# 04_-_SERVO_DRIVER.net
KiCad netlist of a schematic drawn in Altium Designer
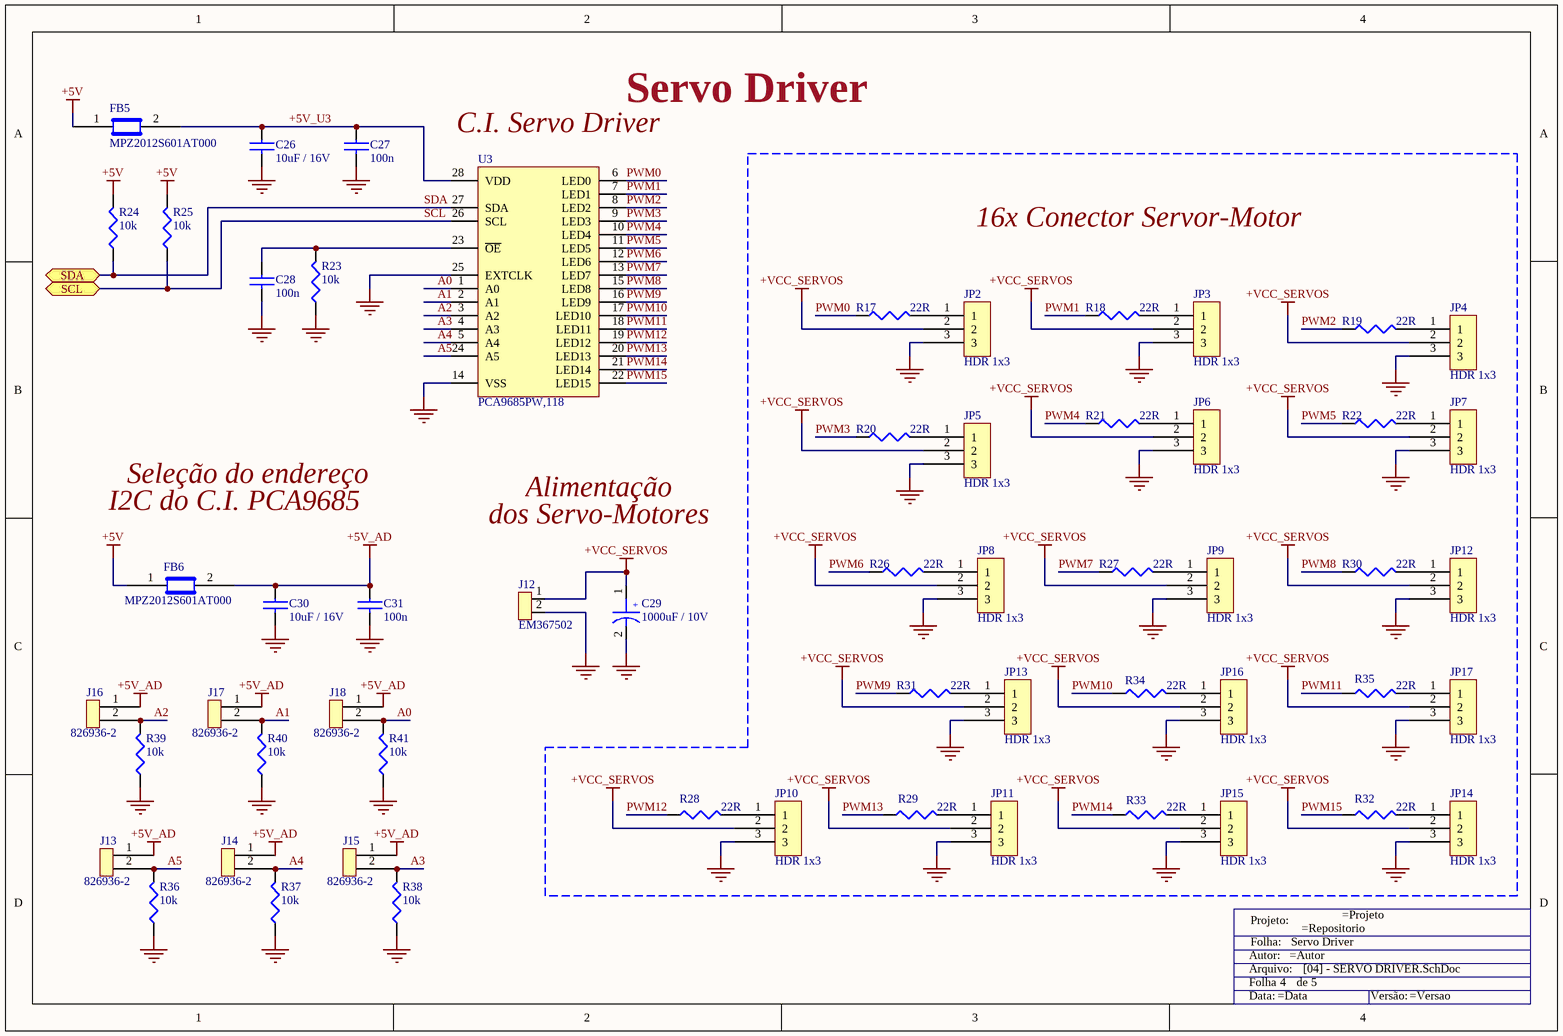
[diagram p0: [04] - SERVO DRIVER.SchDoc]

(export (version "E")
  (design (tool "Eeschema 10.0.6"))
  (components
    (comp (ref "C26")
      (value "10uF / 16V")
      (footprint "C0805")
      (description "CAP CER 10UF 16V X5R 0805")
      (fields
        (field (name "MANUFACTURER") "TDK Corporation")
        (field (name "MANUFACTURER PART NUMBER") "C2012X5R1C106M125AC")
      )
      (libsource (lib "Servo_Control_Lib") (part "C2012X5R1C106M125AC"))
    )
    (comp (ref "C27")
      (value "100n")
      (footprint "C0805")
      (description "CAP CER 0.1UF 50V X7R 0805")
      (fields
        (field (name "MANUFACTURER") "TDK Corporation")
        (field (name "MANUFACTURER PART NUMBER") "C2012X7R1H104K085AA")
      )
      (libsource (lib "Servo_Control_Lib") (part "C2012X7R1H104K085AA_1"))
    )
    (comp (ref "C28")
      (value "100n")
      (footprint "C0805")
      (description "CAP CER 0.1UF 50V X7R 0805")
      (fields
        (field (name "MANUFACTURER") "TDK Corporation")
        (field (name "MANUFACTURER PART NUMBER") "C2012X7R1H104K085AA")
      )
      (libsource (lib "Servo_Control_Lib") (part "C2012X7R1H104K085AA_1"))
    )
    (comp (ref "C29")
      (value "1000uF / 10V")
      (footprint "CAP_EL_10MMX16")
      (description "Aluminum Electrolytic Capacitors - Leaded 10volts 1000uF 10X16")
      (fields
        (field (name "MANUFACTURER") "United Chemi-Con")
        (field (name "MANUFACTURER PART NUMBER") "EKZE100ELL102MJ16S")
      )
      (libsource (lib "Servo_Control_Lib") (part "EKZE100ELL102MJ16S"))
    )
    (comp (ref "C30")
      (value "10uF / 16V")
      (footprint "C0805")
      (description "CAP CER 10UF 16V X5R 0805")
      (fields
        (field (name "MANUFACTURER") "TDK Corporation")
        (field (name "MANUFACTURER PART NUMBER") "C2012X5R1C106M125AC")
      )
      (libsource (lib "Servo_Control_Lib") (part "C2012X5R1C106M125AC"))
    )
    (comp (ref "C31")
      (value "100n")
      (footprint "C0805")
      (description "CAP CER 0.1UF 50V X7R 0805")
      (fields
        (field (name "MANUFACTURER") "TDK Corporation")
        (field (name "MANUFACTURER PART NUMBER") "C2012X7R1H104K085AA")
      )
      (libsource (lib "Servo_Control_Lib") (part "C2012X7R1H104K085AA_1"))
    )
    (comp (ref "FB5")
      (value "MPZ2012S601AT000")
      (footprint "C0805")
      (description "FERRITE CHIP BEAD 600 OHM SMD")
      (fields (field (name "MANUFACTURER") "TDK Corporation"))
      (libsource (lib "Servo_Control_Lib") (part "MPZ2012S601AT000"))
    )
    (comp (ref "FB6")
      (value "MPZ2012S601AT000")
      (footprint "C0805")
      (description "FERRITE CHIP BEAD 600 OHM SMD")
      (fields (field (name "MANUFACTURER") "TDK Corporation"))
      (libsource (lib "Servo_Control_Lib") (part "MPZ2012S601AT000"))
    )
    (comp (ref "J12")
      (value "EM367502")
      (footprint "2_Pins_Fixed_Terminal")
      (description "Fixed Terminal Blocks EURO (MA311-50002) TERM")
      (fields (field (name "MANUFACTURER") "Bussmann / Eaton"))
      (libsource (lib "Servo_Control_Lib") (part "EM367502"))
    )
    (comp (ref "J13")
      (value "826936-2")
      (footprint "HDR_1X2_2.54MM")
      (description "Headers & Wire Housings 2P SINGLE ROW")
      (fields (field (name "MANUFACTURER") "TE Connectivity"))
      (libsource (lib "Servo_Control_Lib") (part "826936-2"))
    )
    (comp (ref "J14")
      (value "826936-2")
      (footprint "HDR_1X2_2.54MM")
      (description "Headers & Wire Housings 2P SINGLE ROW")
      (fields (field (name "MANUFACTURER") "TE Connectivity"))
      (libsource (lib "Servo_Control_Lib") (part "826936-2"))
    )
    (comp (ref "J15")
      (value "826936-2")
      (footprint "HDR_1X2_2.54MM")
      (description "Headers & Wire Housings 2P SINGLE ROW")
      (fields (field (name "MANUFACTURER") "TE Connectivity"))
      (libsource (lib "Servo_Control_Lib") (part "826936-2"))
    )
    (comp (ref "J16")
      (value "826936-2")
      (footprint "HDR_1X2_2.54MM")
      (description "Headers & Wire Housings 2P SINGLE ROW")
      (fields (field (name "MANUFACTURER") "TE Connectivity"))
      (libsource (lib "Servo_Control_Lib") (part "826936-2"))
    )
    (comp (ref "J17")
      (value "826936-2")
      (footprint "HDR_1X2_2.54MM")
      (description "Headers & Wire Housings 2P SINGLE ROW")
      (fields (field (name "MANUFACTURER") "TE Connectivity"))
      (libsource (lib "Servo_Control_Lib") (part "826936-2"))
    )
    (comp (ref "J18")
      (value "826936-2")
      (footprint "HDR_1X2_2.54MM")
      (description "Headers & Wire Housings 2P SINGLE ROW")
      (fields (field (name "MANUFACTURER") "TE Connectivity"))
      (libsource (lib "Servo_Control_Lib") (part "826936-2"))
    )
    (comp (ref "JP2")
      (value "HDR 1x3")
      (footprint "Hdr_1x3_2.54mm")
      (description "BERGSTIK II .100\" SR STRAIGHT")
      (fields (field (name "MANUFACTURER") "FCI") (field (name "MANUFACTURER PART NUMBER") "68000-103HLF"))
      (libsource (lib "Servo_Control_Lib") (part "68000-103HLF"))
    )
    (comp (ref "JP3")
      (value "HDR 1x3")
      (footprint "Hdr_1x3_2.54mm")
      (description "BERGSTIK II .100\" SR STRAIGHT")
      (fields (field (name "MANUFACTURER") "FCI") (field (name "MANUFACTURER PART NUMBER") "68000-103HLF"))
      (libsource (lib "Servo_Control_Lib") (part "68000-103HLF"))
    )
    (comp (ref "JP4")
      (value "HDR 1x3")
      (footprint "Hdr_1x3_2.54mm")
      (description "BERGSTIK II .100\" SR STRAIGHT")
      (fields (field (name "MANUFACTURER") "FCI") (field (name "MANUFACTURER PART NUMBER") "68000-103HLF"))
      (libsource (lib "Servo_Control_Lib") (part "68000-103HLF"))
    )
    (comp (ref "JP5")
      (value "HDR 1x3")
      (footprint "Hdr_1x3_2.54mm")
      (description "BERGSTIK II .100\" SR STRAIGHT")
      (fields (field (name "MANUFACTURER") "FCI") (field (name "MANUFACTURER PART NUMBER") "68000-103HLF"))
      (libsource (lib "Servo_Control_Lib") (part "68000-103HLF"))
    )
    (comp (ref "JP6")
      (value "HDR 1x3")
      (footprint "Hdr_1x3_2.54mm")
      (description "BERGSTIK II .100\" SR STRAIGHT")
      (fields (field (name "MANUFACTURER") "FCI") (field (name "MANUFACTURER PART NUMBER") "68000-103HLF"))
      (libsource (lib "Servo_Control_Lib") (part "68000-103HLF"))
    )
    (comp (ref "JP7")
      (value "HDR 1x3")
      (footprint "Hdr_1x3_2.54mm")
      (description "BERGSTIK II .100\" SR STRAIGHT")
      (fields (field (name "MANUFACTURER") "FCI") (field (name "MANUFACTURER PART NUMBER") "68000-103HLF"))
      (libsource (lib "Servo_Control_Lib") (part "68000-103HLF"))
    )
    (comp (ref "JP8")
      (value "HDR 1x3")
      (footprint "Hdr_1x3_2.54mm")
      (description "BERGSTIK II .100\" SR STRAIGHT")
      (fields (field (name "MANUFACTURER") "FCI") (field (name "MANUFACTURER PART NUMBER") "68000-103HLF"))
      (libsource (lib "Servo_Control_Lib") (part "68000-103HLF"))
    )
    (comp (ref "JP9")
      (value "HDR 1x3")
      (footprint "Hdr_1x3_2.54mm")
      (description "BERGSTIK II .100\" SR STRAIGHT")
      (fields (field (name "MANUFACTURER") "FCI") (field (name "MANUFACTURER PART NUMBER") "68000-103HLF"))
      (libsource (lib "Servo_Control_Lib") (part "68000-103HLF"))
    )
    (comp (ref "JP10")
      (value "HDR 1x3")
      (footprint "Hdr_1x3_2.54mm")
      (description "BERGSTIK II .100\" SR STRAIGHT")
      (fields (field (name "MANUFACTURER") "FCI") (field (name "MANUFACTURER PART NUMBER") "68000-103HLF"))
      (libsource (lib "Servo_Control_Lib") (part "68000-103HLF"))
    )
    (comp (ref "JP11")
      (value "HDR 1x3")
      (footprint "Hdr_1x3_2.54mm")
      (description "BERGSTIK II .100\" SR STRAIGHT")
      (fields (field (name "MANUFACTURER") "FCI") (field (name "MANUFACTURER PART NUMBER") "68000-103HLF"))
      (libsource (lib "Servo_Control_Lib") (part "68000-103HLF"))
    )
    (comp (ref "JP12")
      (value "HDR 1x3")
      (footprint "Hdr_1x3_2.54mm")
      (description "BERGSTIK II .100\" SR STRAIGHT")
      (fields (field (name "MANUFACTURER") "FCI") (field (name "MANUFACTURER PART NUMBER") "68000-103HLF"))
      (libsource (lib "Servo_Control_Lib") (part "68000-103HLF"))
    )
    (comp (ref "JP13")
      (value "HDR 1x3")
      (footprint "Hdr_1x3_2.54mm")
      (description "BERGSTIK II .100\" SR STRAIGHT")
      (fields (field (name "MANUFACTURER") "FCI") (field (name "MANUFACTURER PART NUMBER") "68000-103HLF"))
      (libsource (lib "Servo_Control_Lib") (part "68000-103HLF"))
    )
    (comp (ref "JP14")
      (value "HDR 1x3")
      (footprint "Hdr_1x3_2.54mm")
      (description "BERGSTIK II .100\" SR STRAIGHT")
      (fields (field (name "MANUFACTURER") "FCI") (field (name "MANUFACTURER PART NUMBER") "68000-103HLF"))
      (libsource (lib "Servo_Control_Lib") (part "68000-103HLF"))
    )
    (comp (ref "JP15")
      (value "HDR 1x3")
      (footprint "Hdr_1x3_2.54mm")
      (description "BERGSTIK II .100\" SR STRAIGHT")
      (fields (field (name "MANUFACTURER") "FCI") (field (name "MANUFACTURER PART NUMBER") "68000-103HLF"))
      (libsource (lib "Servo_Control_Lib") (part "68000-103HLF"))
    )
    (comp (ref "JP16")
      (value "HDR 1x3")
      (footprint "Hdr_1x3_2.54mm")
      (description "BERGSTIK II .100\" SR STRAIGHT")
      (fields (field (name "MANUFACTURER") "FCI") (field (name "MANUFACTURER PART NUMBER") "68000-103HLF"))
      (libsource (lib "Servo_Control_Lib") (part "68000-103HLF"))
    )
    (comp (ref "JP17")
      (value "HDR 1x3")
      (footprint "Hdr_1x3_2.54mm")
      (description "BERGSTIK II .100\" SR STRAIGHT")
      (fields (field (name "MANUFACTURER") "FCI") (field (name "MANUFACTURER PART NUMBER") "68000-103HLF"))
      (libsource (lib "Servo_Control_Lib") (part "68000-103HLF"))
    )
    (comp (ref "R17")
      (value "22R")
      (footprint "R0805")
      (description "RES SMD 22 OHM 1% 1/8W 0805")
      (fields
        (field (name "MANUFACTURER") "Yageo")
        (field (name "MANUFACTURER PART NUMBER") "RC0805FR-0722RL")
      )
      (libsource (lib "Servo_Control_Lib") (part "RC0805FR-0722RL"))
    )
    (comp (ref "R18")
      (value "22R")
      (footprint "R0805")
      (description "RES SMD 22 OHM 1% 1/8W 0805")
      (fields
        (field (name "MANUFACTURER") "Yageo")
        (field (name "MANUFACTURER PART NUMBER") "RC0805FR-0722RL")
      )
      (libsource (lib "Servo_Control_Lib") (part "RC0805FR-0722RL"))
    )
    (comp (ref "R19")
      (value "22R")
      (footprint "R0805")
      (description "RES SMD 22 OHM 1% 1/8W 0805")
      (fields
        (field (name "MANUFACTURER") "Yageo")
        (field (name "MANUFACTURER PART NUMBER") "RC0805FR-0722RL")
      )
      (libsource (lib "Servo_Control_Lib") (part "RC0805FR-0722RL"))
    )
    (comp (ref "R20")
      (value "22R")
      (footprint "R0805")
      (description "RES SMD 22 OHM 1% 1/8W 0805")
      (fields
        (field (name "MANUFACTURER") "Yageo")
        (field (name "MANUFACTURER PART NUMBER") "RC0805FR-0722RL")
      )
      (libsource (lib "Servo_Control_Lib") (part "RC0805FR-0722RL"))
    )
    (comp (ref "R21")
      (value "22R")
      (footprint "R0805")
      (description "RES SMD 22 OHM 1% 1/8W 0805")
      (fields
        (field (name "MANUFACTURER") "Yageo")
        (field (name "MANUFACTURER PART NUMBER") "RC0805FR-0722RL")
      )
      (libsource (lib "Servo_Control_Lib") (part "RC0805FR-0722RL"))
    )
    (comp (ref "R22")
      (value "22R")
      (footprint "R0805")
      (description "RES SMD 22 OHM 1% 1/8W 0805")
      (fields
        (field (name "MANUFACTURER") "Yageo")
        (field (name "MANUFACTURER PART NUMBER") "RC0805FR-0722RL")
      )
      (libsource (lib "Servo_Control_Lib") (part "RC0805FR-0722RL"))
    )
    (comp (ref "R23")
      (value "10k")
      (footprint "R0805")
      (description "RES SMD 10K OHM 1% 1/8W 0805")
      (fields
        (field (name "MANUFACTURER") "Yageo")
        (field (name "MANUFACTURER PART NUMBER") "RC0805FR-0710KL")
      )
      (libsource (lib "Servo_Control_Lib") (part "RC0805FR-0710KL"))
    )
    (comp (ref "R24")
      (value "10k")
      (footprint "R0805")
      (description "RES SMD 10K OHM 1% 1/8W 0805")
      (fields
        (field (name "MANUFACTURER") "Yageo")
        (field (name "MANUFACTURER PART NUMBER") "RC0805FR-0710KL")
      )
      (libsource (lib "Servo_Control_Lib") (part "RC0805FR-0710KL"))
    )
    (comp (ref "R25")
      (value "10k")
      (footprint "R0805")
      (description "RES SMD 10K OHM 1% 1/8W 0805")
      (fields
        (field (name "MANUFACTURER") "Yageo")
        (field (name "MANUFACTURER PART NUMBER") "RC0805FR-0710KL")
      )
      (libsource (lib "Servo_Control_Lib") (part "RC0805FR-0710KL"))
    )
    (comp (ref "R26")
      (value "22R")
      (footprint "R0805")
      (description "RES SMD 22 OHM 1% 1/8W 0805")
      (fields
        (field (name "MANUFACTURER") "Yageo")
        (field (name "MANUFACTURER PART NUMBER") "RC0805FR-0722RL")
      )
      (libsource (lib "Servo_Control_Lib") (part "RC0805FR-0722RL"))
    )
    (comp (ref "R27")
      (value "22R")
      (footprint "R0805")
      (description "RES SMD 22 OHM 1% 1/8W 0805")
      (fields
        (field (name "MANUFACTURER") "Yageo")
        (field (name "MANUFACTURER PART NUMBER") "RC0805FR-0722RL")
      )
      (libsource (lib "Servo_Control_Lib") (part "RC0805FR-0722RL"))
    )
    (comp (ref "R28")
      (value "22R")
      (footprint "R0805")
      (description "RES SMD 22 OHM 1% 1/8W 0805")
      (fields
        (field (name "MANUFACTURER") "Yageo")
        (field (name "MANUFACTURER PART NUMBER") "RC0805FR-0722RL")
      )
      (libsource (lib "Servo_Control_Lib") (part "RC0805FR-0722RL"))
    )
    (comp (ref "R29")
      (value "22R")
      (footprint "R0805")
      (description "RES SMD 22 OHM 1% 1/8W 0805")
      (fields
        (field (name "MANUFACTURER") "Yageo")
        (field (name "MANUFACTURER PART NUMBER") "RC0805FR-0722RL")
      )
      (libsource (lib "Servo_Control_Lib") (part "RC0805FR-0722RL"))
    )
    (comp (ref "R30")
      (value "22R")
      (footprint "R0805")
      (description "RES SMD 22 OHM 1% 1/8W 0805")
      (fields
        (field (name "MANUFACTURER") "Yageo")
        (field (name "MANUFACTURER PART NUMBER") "RC0805FR-0722RL")
      )
      (libsource (lib "Servo_Control_Lib") (part "RC0805FR-0722RL"))
    )
    (comp (ref "R31")
      (value "22R")
      (footprint "R0805")
      (description "RES SMD 22 OHM 1% 1/8W 0805")
      (fields
        (field (name "MANUFACTURER") "Yageo")
        (field (name "MANUFACTURER PART NUMBER") "RC0805FR-0722RL")
      )
      (libsource (lib "Servo_Control_Lib") (part "RC0805FR-0722RL"))
    )
    (comp (ref "R32")
      (value "22R")
      (footprint "R0805")
      (description "RES SMD 22 OHM 1% 1/8W 0805")
      (fields
        (field (name "MANUFACTURER") "Yageo")
        (field (name "MANUFACTURER PART NUMBER") "RC0805FR-0722RL")
      )
      (libsource (lib "Servo_Control_Lib") (part "RC0805FR-0722RL"))
    )
    (comp (ref "R33")
      (value "22R")
      (footprint "R0805")
      (description "RES SMD 22 OHM 1% 1/8W 0805")
      (fields
        (field (name "MANUFACTURER") "Yageo")
        (field (name "MANUFACTURER PART NUMBER") "RC0805FR-0722RL")
      )
      (libsource (lib "Servo_Control_Lib") (part "RC0805FR-0722RL"))
    )
    (comp (ref "R34")
      (value "22R")
      (footprint "R0805")
      (description "RES SMD 22 OHM 1% 1/8W 0805")
      (fields
        (field (name "MANUFACTURER") "Yageo")
        (field (name "MANUFACTURER PART NUMBER") "RC0805FR-0722RL")
      )
      (libsource (lib "Servo_Control_Lib") (part "RC0805FR-0722RL"))
    )
    (comp (ref "R35")
      (value "22R")
      (footprint "R0805")
      (description "RES SMD 22 OHM 1% 1/8W 0805")
      (fields
        (field (name "MANUFACTURER") "Yageo")
        (field (name "MANUFACTURER PART NUMBER") "RC0805FR-0722RL")
      )
      (libsource (lib "Servo_Control_Lib") (part "RC0805FR-0722RL"))
    )
    (comp (ref "R36")
      (value "10k")
      (footprint "R0805")
      (description "RES SMD 10K OHM 1% 1/8W 0805")
      (fields
        (field (name "MANUFACTURER") "Yageo")
        (field (name "MANUFACTURER PART NUMBER") "RC0805FR-0710KL")
      )
      (libsource (lib "Servo_Control_Lib") (part "RC0805FR-0710KL"))
    )
    (comp (ref "R37")
      (value "10k")
      (footprint "R0805")
      (description "RES SMD 10K OHM 1% 1/8W 0805")
      (fields
        (field (name "MANUFACTURER") "Yageo")
        (field (name "MANUFACTURER PART NUMBER") "RC0805FR-0710KL")
      )
      (libsource (lib "Servo_Control_Lib") (part "RC0805FR-0710KL"))
    )
    (comp (ref "R38")
      (value "10k")
      (footprint "R0805")
      (description "RES SMD 10K OHM 1% 1/8W 0805")
      (fields
        (field (name "MANUFACTURER") "Yageo")
        (field (name "MANUFACTURER PART NUMBER") "RC0805FR-0710KL")
      )
      (libsource (lib "Servo_Control_Lib") (part "RC0805FR-0710KL"))
    )
    (comp (ref "R39")
      (value "10k")
      (footprint "R0805")
      (description "RES SMD 10K OHM 1% 1/8W 0805")
      (fields
        (field (name "MANUFACTURER") "Yageo")
        (field (name "MANUFACTURER PART NUMBER") "RC0805FR-0710KL")
      )
      (libsource (lib "Servo_Control_Lib") (part "RC0805FR-0710KL"))
    )
    (comp (ref "R40")
      (value "10k")
      (footprint "R0805")
      (description "RES SMD 10K OHM 1% 1/8W 0805")
      (fields
        (field (name "MANUFACTURER") "Yageo")
        (field (name "MANUFACTURER PART NUMBER") "RC0805FR-0710KL")
      )
      (libsource (lib "Servo_Control_Lib") (part "RC0805FR-0710KL"))
    )
    (comp (ref "R41")
      (value "10k")
      (footprint "R0805")
      (description "RES SMD 10K OHM 1% 1/8W 0805")
      (fields
        (field (name "MANUFACTURER") "Yageo")
        (field (name "MANUFACTURER PART NUMBER") "RC0805FR-0710KL")
      )
      (libsource (lib "Servo_Control_Lib") (part "RC0805FR-0710KL"))
    )
    (comp (ref "TitleBlock4")
      (value "Title Block")
      (libsource (lib "Servo_Control_Lib") (part "Title Block"))
    )
    (comp (ref "U3")
      (value "PCA9685PW,118")
      (footprint "TSSOP28")
      (description "LED Display Drivers I2C Bus LED Controller 28-Pin")
      (fields (field (name "MANUFACTURER") "NXP Semiconductors"))
      (libsource (lib "Servo_Control_Lib") (part "PCA9685PW118"))
    )
  )
  (nets
    (net (code "1") (name "+5V") (class "Default")
      (node (ref "FB5") (pin "1") (pinfunction "1_1") (pintype "passive"))
      (node (ref "FB6") (pin "1") (pinfunction "1_1") (pintype "passive"))
      (node (ref "R24") (pin "2") (pinfunction "2_2") (pintype "passive"))
      (node (ref "R25") (pin "2") (pinfunction "2_2") (pintype "passive"))
    )
    (net (code "2") (name "+5V_AD") (class "Default")
      (node (ref "C30") (pin "1") (pinfunction "1_1") (pintype "passive"))
      (node (ref "C31") (pin "1") (pinfunction "1_1") (pintype "passive"))
      (node (ref "FB6") (pin "2") (pinfunction "2_2") (pintype "passive"))
      (node (ref "J13") (pin "1") (pinfunction "1_1") (pintype "passive"))
      (node (ref "J14") (pin "1") (pinfunction "1_1") (pintype "passive"))
      (node (ref "J15") (pin "1") (pinfunction "1_1") (pintype "passive"))
      (node (ref "J16") (pin "1") (pinfunction "1_1") (pintype "passive"))
      (node (ref "J17") (pin "1") (pinfunction "1_1") (pintype "passive"))
      (node (ref "J18") (pin "1") (pinfunction "1_1") (pintype "passive"))
    )
    (net (code "3") (name "+VCC_SERVOS") (class "Default")
      (node (ref "C29") (pin "1") (pinfunction "1_1") (pintype "passive"))
      (node (ref "J12") (pin "1") (pinfunction "1_1") (pintype "passive"))
      (node (ref "JP10") (pin "2") (pinfunction "2_2") (pintype "passive"))
      (node (ref "JP11") (pin "2") (pinfunction "2_2") (pintype "passive"))
      (node (ref "JP12") (pin "2") (pinfunction "2_2") (pintype "passive"))
      (node (ref "JP13") (pin "2") (pinfunction "2_2") (pintype "passive"))
      (node (ref "JP14") (pin "2") (pinfunction "2_2") (pintype "passive"))
      (node (ref "JP15") (pin "2") (pinfunction "2_2") (pintype "passive"))
      (node (ref "JP16") (pin "2") (pinfunction "2_2") (pintype "passive"))
      (node (ref "JP17") (pin "2") (pinfunction "2_2") (pintype "passive"))
      (node (ref "JP2") (pin "2") (pinfunction "2_2") (pintype "passive"))
      (node (ref "JP3") (pin "2") (pinfunction "2_2") (pintype "passive"))
      (node (ref "JP4") (pin "2") (pinfunction "2_2") (pintype "passive"))
      (node (ref "JP5") (pin "2") (pinfunction "2_2") (pintype "passive"))
      (node (ref "JP6") (pin "2") (pinfunction "2_2") (pintype "passive"))
      (node (ref "JP7") (pin "2") (pinfunction "2_2") (pintype "passive"))
      (node (ref "JP8") (pin "2") (pinfunction "2_2") (pintype "passive"))
      (node (ref "JP9") (pin "2") (pinfunction "2_2") (pintype "passive"))
    )
    (net (code "4") (name "/+5V_U3") (class "Default")
      (node (ref "C26") (pin "1") (pinfunction "1_1") (pintype "passive"))
      (node (ref "C27") (pin "1") (pinfunction "1_1") (pintype "passive"))
      (node (ref "FB5") (pin "2") (pinfunction "2_2") (pintype "passive"))
      (node (ref "U3") (pin "28") (pinfunction "VDD_28") (pintype "passive"))
    )
    (net (code "5") (name "/A0") (class "Default")
      (node (ref "J18") (pin "2") (pinfunction "2_2") (pintype "passive"))
      (node (ref "R41") (pin "2") (pinfunction "2_2") (pintype "passive"))
      (node (ref "U3") (pin "1") (pinfunction "A0_1") (pintype "passive"))
    )
    (net (code "6") (name "/A1") (class "Default")
      (node (ref "J17") (pin "2") (pinfunction "2_2") (pintype "passive"))
      (node (ref "R40") (pin "2") (pinfunction "2_2") (pintype "passive"))
      (node (ref "U3") (pin "2") (pinfunction "A1_2") (pintype "passive"))
    )
    (net (code "7") (name "/A2") (class "Default")
      (node (ref "J16") (pin "2") (pinfunction "2_2") (pintype "passive"))
      (node (ref "R39") (pin "2") (pinfunction "2_2") (pintype "passive"))
      (node (ref "U3") (pin "3") (pinfunction "A2_3") (pintype "passive"))
    )
    (net (code "8") (name "/A3") (class "Default")
      (node (ref "J15") (pin "2") (pinfunction "2_2") (pintype "passive"))
      (node (ref "R38") (pin "2") (pinfunction "2_2") (pintype "passive"))
      (node (ref "U3") (pin "4") (pinfunction "A3_4") (pintype "passive"))
    )
    (net (code "9") (name "/A4") (class "Default")
      (node (ref "J14") (pin "2") (pinfunction "2_2") (pintype "passive"))
      (node (ref "R37") (pin "2") (pinfunction "2_2") (pintype "passive"))
      (node (ref "U3") (pin "5") (pinfunction "A4_5") (pintype "passive"))
    )
    (net (code "10") (name "/A5") (class "Default")
      (node (ref "J13") (pin "2") (pinfunction "2_2") (pintype "passive"))
      (node (ref "R36") (pin "2") (pinfunction "2_2") (pintype "passive"))
      (node (ref "U3") (pin "24") (pinfunction "A5_24") (pintype "passive"))
    )
    (net (code "11") (name "/PWM0") (class "Default")
      (node (ref "R17") (pin "1") (pinfunction "1_1") (pintype "passive"))
      (node (ref "U3") (pin "6") (pinfunction "LED0_6") (pintype "passive"))
    )
    (net (code "12") (name "/PWM1") (class "Default")
      (node (ref "R18") (pin "1") (pinfunction "1_1") (pintype "passive"))
      (node (ref "U3") (pin "7") (pinfunction "LED1_7") (pintype "passive"))
    )
    (net (code "13") (name "/PWM2") (class "Default")
      (node (ref "R19") (pin "1") (pinfunction "1_1") (pintype "passive"))
      (node (ref "U3") (pin "8") (pinfunction "LED2_8") (pintype "passive"))
    )
    (net (code "14") (name "/PWM3") (class "Default")
      (node (ref "R20") (pin "1") (pinfunction "1_1") (pintype "passive"))
      (node (ref "U3") (pin "9") (pinfunction "LED3_9") (pintype "passive"))
    )
    (net (code "15") (name "/PWM4") (class "Default")
      (node (ref "R21") (pin "1") (pinfunction "1_1") (pintype "passive"))
      (node (ref "U3") (pin "10") (pinfunction "LED4_10") (pintype "passive"))
    )
    (net (code "16") (name "/PWM5") (class "Default")
      (node (ref "R22") (pin "1") (pinfunction "1_1") (pintype "passive"))
      (node (ref "U3") (pin "11") (pinfunction "LED5_11") (pintype "passive"))
    )
    (net (code "17") (name "/PWM6") (class "Default")
      (node (ref "R26") (pin "1") (pinfunction "1_1") (pintype "passive"))
      (node (ref "U3") (pin "12") (pinfunction "LED6_12") (pintype "passive"))
    )
    (net (code "18") (name "/PWM7") (class "Default")
      (node (ref "R27") (pin "1") (pinfunction "1_1") (pintype "passive"))
      (node (ref "U3") (pin "13") (pinfunction "LED7_13") (pintype "passive"))
    )
    (net (code "19") (name "/PWM8") (class "Default")
      (node (ref "R30") (pin "1") (pinfunction "1_1") (pintype "passive"))
      (node (ref "U3") (pin "15") (pinfunction "LED8_15") (pintype "passive"))
    )
    (net (code "20") (name "/PWM9") (class "Default")
      (node (ref "R31") (pin "1") (pinfunction "1_1") (pintype "passive"))
      (node (ref "U3") (pin "16") (pinfunction "LED9_16") (pintype "passive"))
    )
    (net (code "21") (name "/PWM10") (class "Default")
      (node (ref "R34") (pin "1") (pinfunction "1_1") (pintype "passive"))
      (node (ref "U3") (pin "17") (pinfunction "LED10_17") (pintype "passive"))
    )
    (net (code "22") (name "/PWM11") (class "Default")
      (node (ref "R35") (pin "1") (pinfunction "1_1") (pintype "passive"))
      (node (ref "U3") (pin "18") (pinfunction "LED11_18") (pintype "passive"))
    )
    (net (code "23") (name "/PWM12") (class "Default")
      (node (ref "R28") (pin "1") (pinfunction "1_1") (pintype "passive"))
      (node (ref "U3") (pin "19") (pinfunction "LED12_19") (pintype "passive"))
    )
    (net (code "24") (name "/PWM13") (class "Default")
      (node (ref "R29") (pin "1") (pinfunction "1_1") (pintype "passive"))
      (node (ref "U3") (pin "20") (pinfunction "LED13_20") (pintype "passive"))
    )
    (net (code "25") (name "/PWM14") (class "Default")
      (node (ref "R33") (pin "1") (pinfunction "1_1") (pintype "passive"))
      (node (ref "U3") (pin "21") (pinfunction "LED14_21") (pintype "passive"))
    )
    (net (code "26") (name "/PWM15") (class "Default")
      (node (ref "R32") (pin "1") (pinfunction "1_1") (pintype "passive"))
      (node (ref "U3") (pin "22") (pinfunction "LED15_22") (pintype "passive"))
    )
    (net (code "27") (name "/SCL") (class "Default")
      (node (ref "R25") (pin "1") (pinfunction "1_1") (pintype "passive"))
      (node (ref "U3") (pin "26") (pinfunction "SCL_26") (pintype "passive"))
    )
    (net (code "28") (name "/SDA") (class "Default")
      (node (ref "R24") (pin "1") (pinfunction "1_1") (pintype "passive"))
      (node (ref "U3") (pin "27") (pinfunction "SDA_27") (pintype "passive"))
    )
    (net (code "29") (name "GND") (class "Default")
      (node (ref "C26") (pin "2") (pinfunction "2_2") (pintype "passive"))
      (node (ref "C27") (pin "2") (pinfunction "2_2") (pintype "passive"))
      (node (ref "C28") (pin "2") (pinfunction "2_2") (pintype "passive"))
      (node (ref "C29") (pin "2") (pinfunction "2_2") (pintype "passive"))
      (node (ref "C30") (pin "2") (pinfunction "2_2") (pintype "passive"))
      (node (ref "C31") (pin "2") (pinfunction "2_2") (pintype "passive"))
      (node (ref "J12") (pin "2") (pinfunction "2_2") (pintype "passive"))
      (node (ref "JP10") (pin "3") (pinfunction "3_3") (pintype "passive"))
      (node (ref "JP11") (pin "3") (pinfunction "3_3") (pintype "passive"))
      (node (ref "JP12") (pin "3") (pinfunction "3_3") (pintype "passive"))
      (node (ref "JP13") (pin "3") (pinfunction "3_3") (pintype "passive"))
      (node (ref "JP14") (pin "3") (pinfunction "3_3") (pintype "passive"))
      (node (ref "JP15") (pin "3") (pinfunction "3_3") (pintype "passive"))
      (node (ref "JP16") (pin "3") (pinfunction "3_3") (pintype "passive"))
      (node (ref "JP17") (pin "3") (pinfunction "3_3") (pintype "passive"))
      (node (ref "JP2") (pin "3") (pinfunction "3_3") (pintype "passive"))
      (node (ref "JP3") (pin "3") (pinfunction "3_3") (pintype "passive"))
      (node (ref "JP4") (pin "3") (pinfunction "3_3") (pintype "passive"))
      (node (ref "JP5") (pin "3") (pinfunction "3_3") (pintype "passive"))
      (node (ref "JP6") (pin "3") (pinfunction "3_3") (pintype "passive"))
      (node (ref "JP7") (pin "3") (pinfunction "3_3") (pintype "passive"))
      (node (ref "JP8") (pin "3") (pinfunction "3_3") (pintype "passive"))
      (node (ref "JP9") (pin "3") (pinfunction "3_3") (pintype "passive"))
      (node (ref "R23") (pin "1") (pinfunction "1_1") (pintype "passive"))
      (node (ref "R36") (pin "1") (pinfunction "1_1") (pintype "passive"))
      (node (ref "R37") (pin "1") (pinfunction "1_1") (pintype "passive"))
      (node (ref "R38") (pin "1") (pinfunction "1_1") (pintype "passive"))
      (node (ref "R39") (pin "1") (pinfunction "1_1") (pintype "passive"))
      (node (ref "R40") (pin "1") (pinfunction "1_1") (pintype "passive"))
      (node (ref "R41") (pin "1") (pinfunction "1_1") (pintype "passive"))
      (node (ref "U3") (pin "14") (pinfunction "VSS_14") (pintype "passive"))
      (node (ref "U3") (pin "25") (pinfunction "EXTCLK_25") (pintype "passive"))
    )
    (net (code "30") (name "Net-(JP2-Pad1)") (class "Default")
      (node (ref "JP2") (pin "1") (pinfunction "1_1") (pintype "passive"))
      (node (ref "R17") (pin "2") (pinfunction "2_2") (pintype "passive"))
    )
    (net (code "31") (name "Net-(JP3-Pad1)") (class "Default")
      (node (ref "JP3") (pin "1") (pinfunction "1_1") (pintype "passive"))
      (node (ref "R18") (pin "2") (pinfunction "2_2") (pintype "passive"))
    )
    (net (code "32") (name "Net-(JP4-Pad1)") (class "Default")
      (node (ref "JP4") (pin "1") (pinfunction "1_1") (pintype "passive"))
      (node (ref "R19") (pin "2") (pinfunction "2_2") (pintype "passive"))
    )
    (net (code "33") (name "Net-(JP5-Pad1)") (class "Default")
      (node (ref "JP5") (pin "1") (pinfunction "1_1") (pintype "passive"))
      (node (ref "R20") (pin "2") (pinfunction "2_2") (pintype "passive"))
    )
    (net (code "34") (name "Net-(JP6-Pad1)") (class "Default")
      (node (ref "JP6") (pin "1") (pinfunction "1_1") (pintype "passive"))
      (node (ref "R21") (pin "2") (pinfunction "2_2") (pintype "passive"))
    )
    (net (code "35") (name "Net-(JP7-Pad1)") (class "Default")
      (node (ref "JP7") (pin "1") (pinfunction "1_1") (pintype "passive"))
      (node (ref "R22") (pin "2") (pinfunction "2_2") (pintype "passive"))
    )
    (net (code "36") (name "Net-(JP8-Pad1)") (class "Default")
      (node (ref "JP8") (pin "1") (pinfunction "1_1") (pintype "passive"))
      (node (ref "R26") (pin "2") (pinfunction "2_2") (pintype "passive"))
    )
    (net (code "37") (name "Net-(JP9-Pad1)") (class "Default")
      (node (ref "JP9") (pin "1") (pinfunction "1_1") (pintype "passive"))
      (node (ref "R27") (pin "2") (pinfunction "2_2") (pintype "passive"))
    )
    (net (code "38") (name "Net-(JP10-Pad1)") (class "Default")
      (node (ref "JP10") (pin "1") (pinfunction "1_1") (pintype "passive"))
      (node (ref "R28") (pin "2") (pinfunction "2_2") (pintype "passive"))
    )
    (net (code "39") (name "Net-(JP11-Pad1)") (class "Default")
      (node (ref "JP11") (pin "1") (pinfunction "1_1") (pintype "passive"))
      (node (ref "R29") (pin "2") (pinfunction "2_2") (pintype "passive"))
    )
    (net (code "40") (name "Net-(JP12-Pad1)") (class "Default")
      (node (ref "JP12") (pin "1") (pinfunction "1_1") (pintype "passive"))
      (node (ref "R30") (pin "2") (pinfunction "2_2") (pintype "passive"))
    )
    (net (code "41") (name "Net-(JP13-Pad1)") (class "Default")
      (node (ref "JP13") (pin "1") (pinfunction "1_1") (pintype "passive"))
      (node (ref "R31") (pin "2") (pinfunction "2_2") (pintype "passive"))
    )
    (net (code "42") (name "Net-(JP14-Pad1)") (class "Default")
      (node (ref "JP14") (pin "1") (pinfunction "1_1") (pintype "passive"))
      (node (ref "R32") (pin "2") (pinfunction "2_2") (pintype "passive"))
    )
    (net (code "43") (name "Net-(JP15-Pad1)") (class "Default")
      (node (ref "JP15") (pin "1") (pinfunction "1_1") (pintype "passive"))
      (node (ref "R33") (pin "2") (pinfunction "2_2") (pintype "passive"))
    )
    (net (code "44") (name "Net-(JP16-Pad1)") (class "Default")
      (node (ref "JP16") (pin "1") (pinfunction "1_1") (pintype "passive"))
      (node (ref "R34") (pin "2") (pinfunction "2_2") (pintype "passive"))
    )
    (net (code "45") (name "Net-(JP17-Pad1)") (class "Default")
      (node (ref "JP17") (pin "1") (pinfunction "1_1") (pintype "passive"))
      (node (ref "R35") (pin "2") (pinfunction "2_2") (pintype "passive"))
    )
    (net (code "46") (name "Net-(U3-~{OE})") (class "Default")
      (node (ref "C28") (pin "1") (pinfunction "1_1") (pintype "passive"))
      (node (ref "R23") (pin "2") (pinfunction "2_2") (pintype "passive"))
      (node (ref "U3") (pin "23") (pinfunction "~{OE}_23") (pintype "passive"))
    )
  )
)
